# buck_reg_12v_6a.net
KiCad netlist of a schematic drawn in Altium Designer
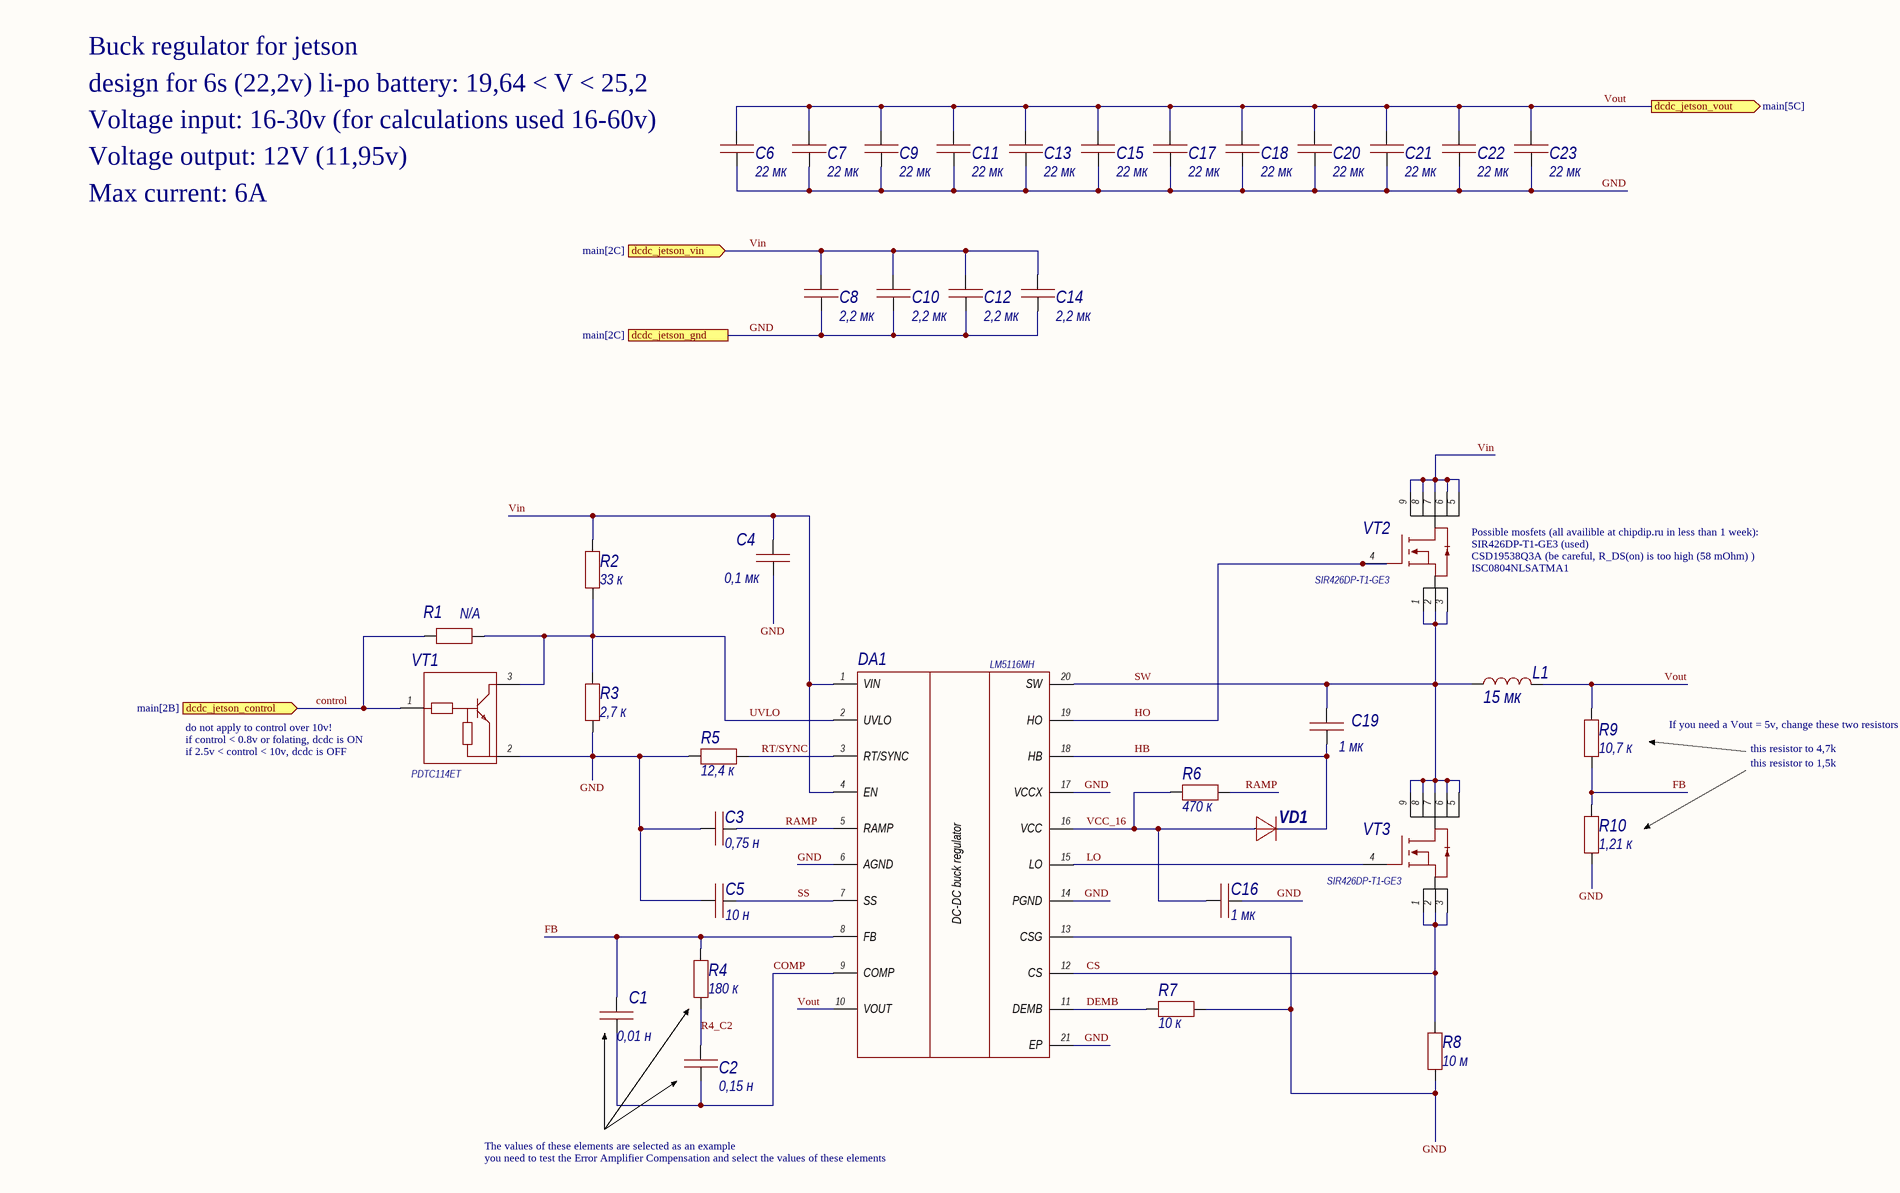
[diagram p0: buck_reg_12v_6a.SchDoc, top left]
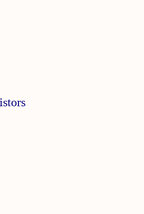
[diagram p1: buck_reg_12v_6a.SchDoc, top right]
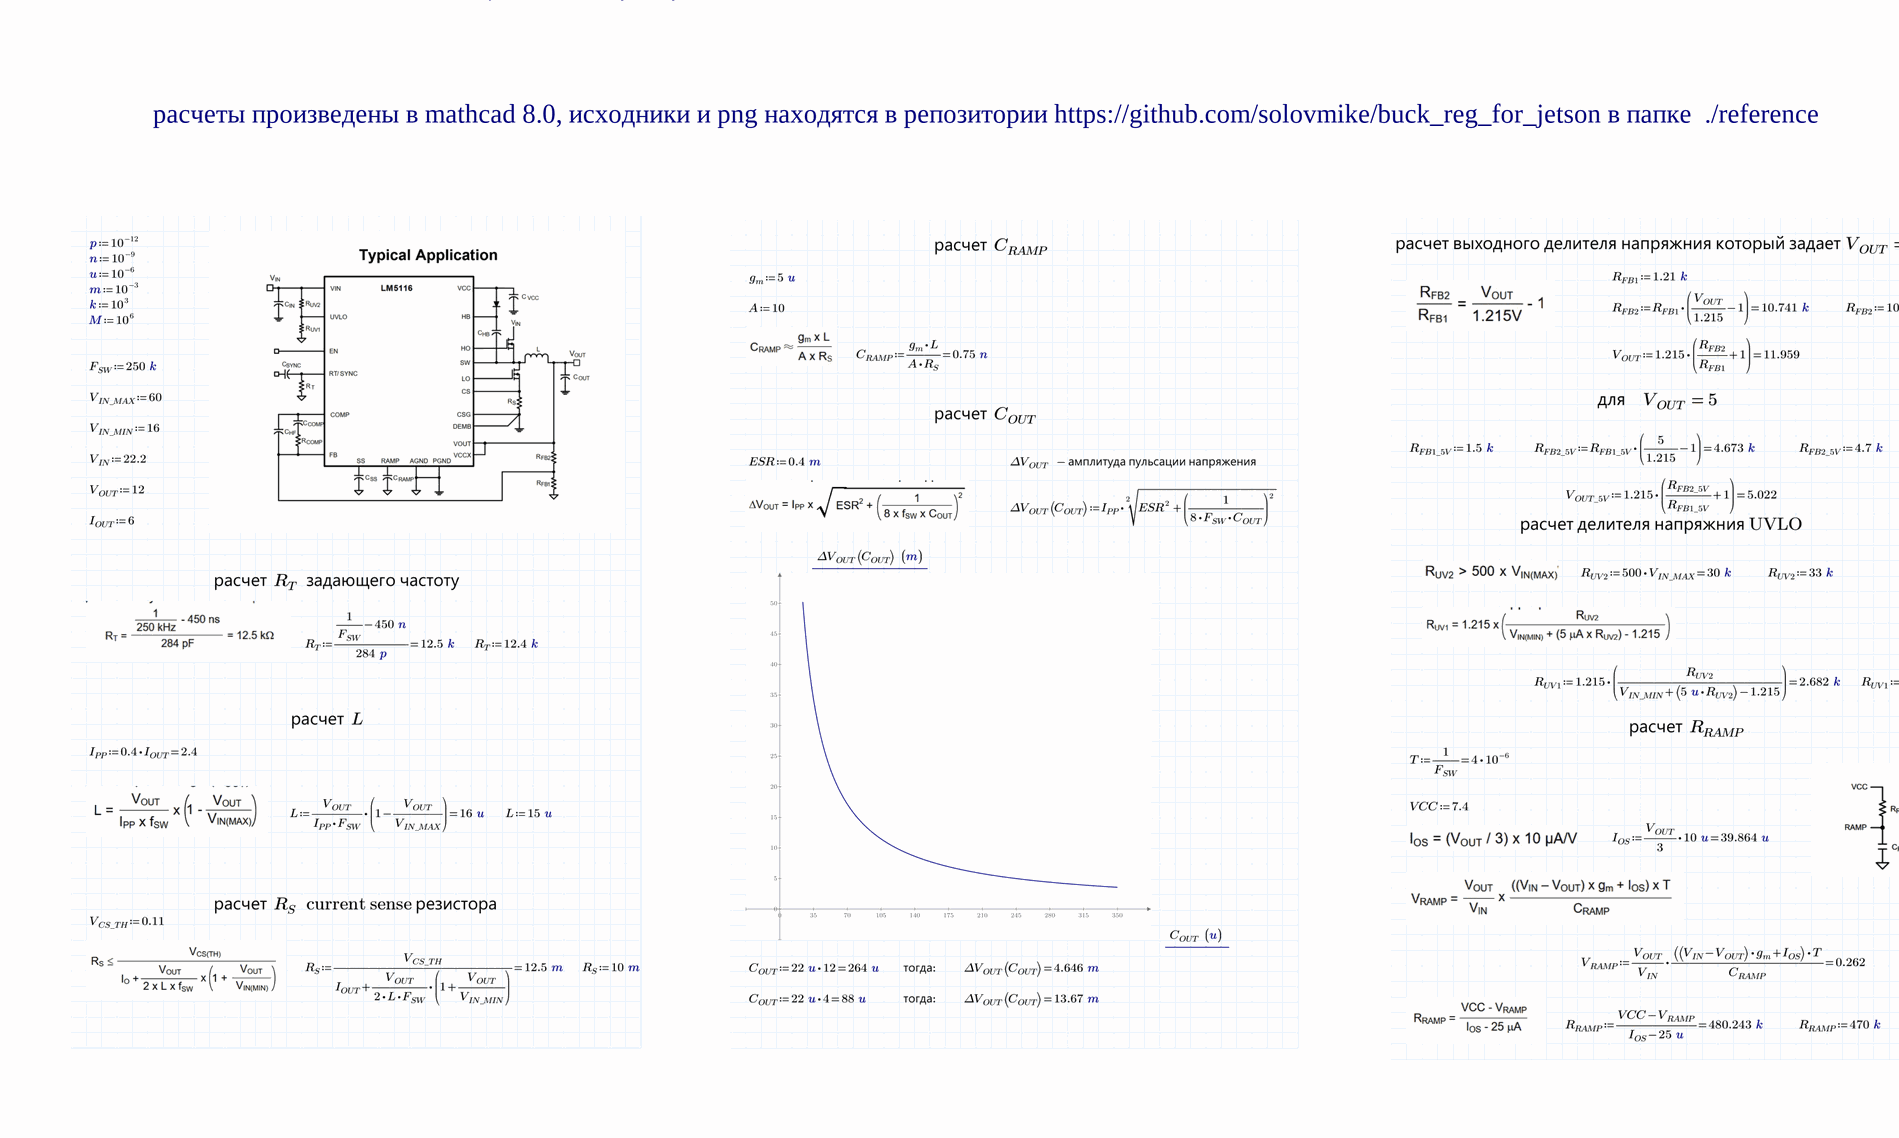
[diagram p2: buck_reg_12v_6a.SchDoc, bottom left]
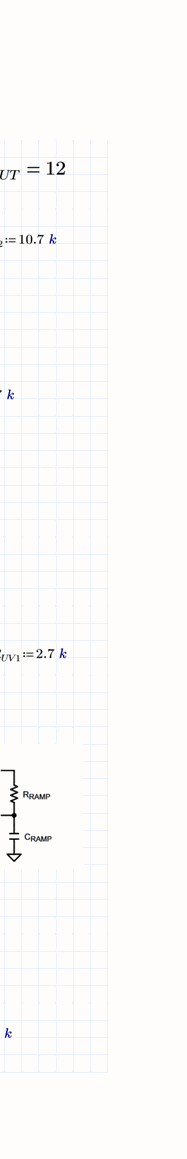
[diagram p3: buck_reg_12v_6a.SchDoc, bottom right]

(export (version "E")
  (design (tool "Eeschema 10.0.6"))
  (components
    (comp (ref "C1")
      (value "0,01 н")
      (footprint "0603C")
      (description "Конденсатор")
      (fields
        (field (name "PART NUMBER") "Capacitor_0,01n_10_50V_X7R_0603C")
        (field (name "TOLERANCE") "0,1")
      )
      (libsource (lib "Hydrolib") (part "Capacitor"))
    )
    (comp (ref "C2")
      (value "0,15 н")
      (footprint "0603C")
      (description "Конденсатор")
      (fields
        (field (name "PART NUMBER") "Capacitor_0,15n_10_50V_X7R_0603C")
        (field (name "TOLERANCE") "0,1")
      )
      (libsource (lib "Hydrolib") (part "Capacitor"))
    )
    (comp (ref "C3")
      (value "0,75 н")
      (footprint "0603C")
      (description "Конденсатор")
      (fields
        (field (name "PART NUMBER") "Capacitor_0,75n_10_50V_X7R_0603C")
        (field (name "TOLERANCE") "0,1")
      )
      (libsource (lib "Hydrolib") (part "Capacitor"))
    )
    (comp (ref "C4")
      (value "0,1 мк")
      (footprint "0603C")
      (description "Конденсатор")
      (fields (field (name "PART NUMBER") "Capacitor_0,1u_10_50V_X7R_0603C") (field (name "TOLERANCE") "0,1"))
      (libsource (lib "Hydrolib") (part "Capacitor"))
    )
    (comp (ref "C5")
      (value "10 н")
      (footprint "0603C")
      (description "Конденсатор")
      (fields (field (name "PART NUMBER") "Capacitor_10n_10_50V_X7R_0603C") (field (name "TOLERANCE") "0,1"))
      (libsource (lib "Hydrolib") (part "Capacitor"))
    )
    (comp (ref "C6")
      (value "22 мк")
      (footprint "1210C")
      (description "Конденсатор")
      (fields (field (name "PART NUMBER") "Capacitor_22u_10_25V_X7R_1210C") (field (name "TOLERANCE") "0,1"))
      (libsource (lib "Hydrolib") (part "Capacitor"))
    )
    (comp (ref "C7")
      (value "22 мк")
      (footprint "1210C")
      (description "Конденсатор")
      (fields (field (name "PART NUMBER") "Capacitor_22u_10_25V_X7R_1210C") (field (name "TOLERANCE") "0,1"))
      (libsource (lib "Hydrolib") (part "Capacitor"))
    )
    (comp (ref "C8")
      (value "2,2 мк")
      (footprint "1206C")
      (description "Конденсатор")
      (fields (field (name "PART NUMBER") "Capacitor_2,2u_10_50V_X7R_1206C") (field (name "TOLERANCE") "0,1"))
      (libsource (lib "Hydrolib") (part "Capacitor"))
    )
    (comp (ref "C9")
      (value "22 мк")
      (footprint "1210C")
      (description "Конденсатор")
      (fields (field (name "PART NUMBER") "Capacitor_22u_10_25V_X7R_1210C") (field (name "TOLERANCE") "0,1"))
      (libsource (lib "Hydrolib") (part "Capacitor"))
    )
    (comp (ref "C10")
      (value "2,2 мк")
      (footprint "1206C")
      (description "Конденсатор")
      (fields (field (name "PART NUMBER") "Capacitor_2,2u_10_50V_X7R_1206C") (field (name "TOLERANCE") "0,1"))
      (libsource (lib "Hydrolib") (part "Capacitor"))
    )
    (comp (ref "C11")
      (value "22 мк")
      (footprint "1210C")
      (description "Конденсатор")
      (fields (field (name "PART NUMBER") "Capacitor_22u_10_25V_X7R_1210C") (field (name "TOLERANCE") "0,1"))
      (libsource (lib "Hydrolib") (part "Capacitor"))
    )
    (comp (ref "C12")
      (value "2,2 мк")
      (footprint "1206C")
      (description "Конденсатор")
      (fields (field (name "PART NUMBER") "Capacitor_2,2u_10_50V_X7R_1206C") (field (name "TOLERANCE") "0,1"))
      (libsource (lib "Hydrolib") (part "Capacitor"))
    )
    (comp (ref "C13")
      (value "22 мк")
      (footprint "1210C")
      (description "Конденсатор")
      (fields (field (name "PART NUMBER") "Capacitor_22u_10_25V_X7R_1210C") (field (name "TOLERANCE") "0,1"))
      (libsource (lib "Hydrolib") (part "Capacitor"))
    )
    (comp (ref "C14")
      (value "2,2 мк")
      (footprint "1206C")
      (description "Конденсатор")
      (fields (field (name "PART NUMBER") "Capacitor_2,2u_10_50V_X7R_1206C") (field (name "TOLERANCE") "0,1"))
      (libsource (lib "Hydrolib") (part "Capacitor"))
    )
    (comp (ref "C15")
      (value "22 мк")
      (footprint "1210C")
      (description "Конденсатор")
      (fields (field (name "PART NUMBER") "Capacitor_22u_10_25V_X7R_1210C") (field (name "TOLERANCE") "0,1"))
      (libsource (lib "Hydrolib") (part "Capacitor"))
    )
    (comp (ref "C16")
      (value "1 мк")
      (footprint "0603C")
      (description "Конденсатор")
      (fields (field (name "PART NUMBER") "Capacitor_1u_10_50V_X7R_0603C") (field (name "TOLERANCE") "0,1"))
      (libsource (lib "Hydrolib") (part "Capacitor"))
    )
    (comp (ref "C17")
      (value "22 мк")
      (footprint "1210C")
      (description "Конденсатор")
      (fields (field (name "PART NUMBER") "Capacitor_22u_10_25V_X7R_1210C") (field (name "TOLERANCE") "0,1"))
      (libsource (lib "Hydrolib") (part "Capacitor"))
    )
    (comp (ref "C18")
      (value "22 мк")
      (footprint "1210C")
      (description "Конденсатор")
      (fields (field (name "PART NUMBER") "Capacitor_22u_10_25V_X7R_1210C") (field (name "TOLERANCE") "0,1"))
      (libsource (lib "Hydrolib") (part "Capacitor"))
    )
    (comp (ref "C19")
      (value "1 мк")
      (footprint "0603C")
      (description "Конденсатор")
      (fields (field (name "PART NUMBER") "Capacitor_1u_10_50V_X7R_0603C") (field (name "TOLERANCE") "0,1"))
      (libsource (lib "Hydrolib") (part "Capacitor"))
    )
    (comp (ref "C20")
      (value "22 мк")
      (footprint "1210C")
      (description "Конденсатор")
      (fields (field (name "PART NUMBER") "Capacitor_22u_10_25V_X7R_1210C") (field (name "TOLERANCE") "0,1"))
      (libsource (lib "Hydrolib") (part "Capacitor"))
    )
    (comp (ref "C21")
      (value "22 мк")
      (footprint "1210C")
      (description "Конденсатор")
      (fields (field (name "PART NUMBER") "Capacitor_22u_10_25V_X7R_1210C") (field (name "TOLERANCE") "0,1"))
      (libsource (lib "Hydrolib") (part "Capacitor"))
    )
    (comp (ref "C22")
      (value "22 мк")
      (footprint "1210C")
      (description "Конденсатор")
      (fields (field (name "PART NUMBER") "Capacitor_22u_10_25V_X7R_1210C") (field (name "TOLERANCE") "0,1"))
      (libsource (lib "Hydrolib") (part "Capacitor"))
    )
    (comp (ref "C23")
      (value "22 мк")
      (footprint "1210C")
      (description "Конденсатор")
      (fields (field (name "PART NUMBER") "Capacitor_22u_10_25V_X7R_1210C") (field (name "TOLERANCE") "0,1"))
      (libsource (lib "Hydrolib") (part "Capacitor"))
    )
    (comp (ref "DA1")
      (value "LM5116MH")
      (footprint "HTSSOP-20")
      (description "dc-dc понижающий adj 6-100v")
      (fields (field (name "MANUFACTURER_PART_NUMBER") "LM5116MH/NOPB"))
      (libsource (lib "Hydrolib") (part "LM5116MH"))
    )
    (comp (ref "L1")
      (value "15 мк")
      (footprint "SPRH127")
      (description "Индуктивность на 15 мкГн, номинальный ток 8,4 А")
      (fields (field (name "PART NUMBER") "CDSPRH127-150M"))
      (libsource (lib "Hydrolib") (part "Inductance"))
    )
    (comp (ref "R1")
      (value "N/A")
      (footprint "0603R")
      (description "посадочное место 0603 под перемычку")
      (fields (field (name "PART NUMBER") "res_0603_N/A") (field (name "TOLERANCE") "1%"))
      (libsource (lib "") (part "Resistor_1"))
    )
    (comp (ref "R2")
      (value "33 к")
      (footprint "0603R")
      (description "Резистор номиналом 33 кОм и точностью 1%")
      (fields (field (name "PART NUMBER") "Resistor_33k_1_0603") (field (name "TOLERANCE") "1%"))
      (libsource (lib "Hydrolib") (part "Resistor"))
    )
    (comp (ref "R3")
      (value "2,7 к")
      (footprint "0603R")
      (description "Резистор номиналом 2,7 кОм и точностью 1%")
      (fields (field (name "PART NUMBER") "Resistor_2.7k_1_0603") (field (name "TOLERANCE") "1%"))
      (libsource (lib "Hydrolib") (part "Resistor"))
    )
    (comp (ref "R4")
      (value "180 к")
      (footprint "0603R")
      (description "Резистор номиналом 180 кОм и точностью 1%")
      (fields (field (name "PART NUMBER") "Resistor_180k_1_0603") (field (name "TOLERANCE") "1%"))
      (libsource (lib "Hydrolib") (part "Resistor"))
    )
    (comp (ref "R5")
      (value "12,4 к")
      (footprint "0603R")
      (description "Резистор номиналом 12,4 кОм и точностью 1%")
      (fields (field (name "PART NUMBER") "Resistor_12.4k_1_0603") (field (name "TOLERANCE") "1%"))
      (libsource (lib "") (part "Resistor_1"))
    )
    (comp (ref "R6")
      (value "470 к")
      (footprint "0603R")
      (description "Резистор номиналом 470 кОм и точностью 1%")
      (fields (field (name "PART NUMBER") "Resistor_470k_1_0603") (field (name "TOLERANCE") "1%"))
      (libsource (lib "") (part "Resistor_1"))
    )
    (comp (ref "R7")
      (value "10 к")
      (footprint "0603R")
      (description "Резистор номиналом 10 кОм и точностью 1%")
      (fields (field (name "PART NUMBER") "Resistor_10k_1_0603") (field (name "TOLERANCE") "1%"))
      (libsource (lib "") (part "Resistor_1"))
    )
    (comp (ref "R8")
      (value "10 м")
      (footprint "1210R")
      (description "Резистор номиналом 10 мОм, точностью 1%, 0.5Вт")
      (fields (field (name "PART NUMBER") "RL1210FR-070R01L") (field (name "TOLERANCE") "1%"))
      (libsource (lib "Hydrolib") (part "Resistor"))
    )
    (comp (ref "R9")
      (value "10,7 к")
      (footprint "0603R")
      (description "Резистор номиналом 10,7 кОм и точностью 1%")
      (fields (field (name "PART NUMBER") "Resistor_10.7k_1_0603") (field (name "TOLERANCE") "1%"))
      (libsource (lib "Hydrolib") (part "Resistor"))
    )
    (comp (ref "R10")
      (value "1,21 к")
      (footprint "0603R")
      (description "Резистор номиналом 1,21 кОм и точностью 1%")
      (fields (field (name "PART NUMBER") "Resistor_1.21k_1_0603") (field (name "TOLERANCE") "1%"))
      (libsource (lib "Hydrolib") (part "Resistor"))
    )
    (comp (ref "VD1")
      (value "ES1D-E3/61T")
      (footprint "SMA")
      (description "Диод 1A 200V")
      (libsource (lib "Hydrolib") (part "Rectifier_diode"))
    )
    (comp (ref "VT1")
      (value "PDTC114ET")
      (footprint "SOT23-3")
      (description "цифровой npn 50в 100мА")
      (libsource (lib "Hydrolib") (part "PDTC114ET"))
    )
    (comp (ref "VT2")
      (value "SIR426DP-T1-GE3")
      (footprint "PowerPAK_SO-8")
      (description "Транзистор полевой MOSFET N-канальный 40В 41.7Вт")
      (libsource (lib "Hydrolib") (part "SIR426DP-T1-GE3"))
    )
    (comp (ref "VT3")
      (value "SIR426DP-T1-GE3")
      (footprint "PowerPAK_SO-8")
      (description "Транзистор полевой MOSFET N-канальный 40В 41.7Вт")
      (libsource (lib "Hydrolib") (part "SIR426DP-T1-GE3"))
    )
  )
  (nets
    (net (code "1") (name "/COMP") (class "Default")
      (node (ref "C1") (pin "1") (pinfunction "1_1") (pintype "passive"))
      (node (ref "C2") (pin "1") (pinfunction "1_1") (pintype "passive"))
      (node (ref "DA1") (pin "9") (pinfunction "COMP_9") (pintype "passive"))
    )
    (net (code "2") (name "/CS") (class "Default")
      (node (ref "DA1") (pin "12") (pinfunction "CS_12") (pintype "passive"))
      (node (ref "R8") (pin "2") (pinfunction "2_2") (pintype "passive"))
      (node (ref "VT3") (pin "1") (pinfunction "1_1") (pintype "passive"))
      (node (ref "VT3") (pin "2") (pinfunction "2_2") (pintype "passive"))
      (node (ref "VT3") (pin "3") (pinfunction "3_3") (pintype "passive"))
    )
    (net (code "3") (name "/DEMB") (class "Default")
      (node (ref "DA1") (pin "11") (pinfunction "DEMB_11") (pintype "passive"))
      (node (ref "R7") (pin "1") (pinfunction "1_1") (pintype "passive"))
    )
    (net (code "4") (name "/FB") (class "Default")
      (node (ref "C1") (pin "2") (pinfunction "2_2") (pintype "passive"))
      (node (ref "DA1") (pin "8") (pinfunction "FB_8") (pintype "passive"))
      (node (ref "R10") (pin "2") (pinfunction "2_2") (pintype "passive"))
      (node (ref "R4") (pin "2") (pinfunction "2_2") (pintype "passive"))
      (node (ref "R9") (pin "1") (pinfunction "1_1") (pintype "passive"))
    )
    (net (code "5") (name "/GND") (class "Default")
      (node (ref "C10") (pin "1") (pinfunction "1_1") (pintype "passive"))
      (node (ref "C11") (pin "1") (pinfunction "1_1") (pintype "passive"))
      (node (ref "C12") (pin "1") (pinfunction "1_1") (pintype "passive"))
      (node (ref "C13") (pin "1") (pinfunction "1_1") (pintype "passive"))
      (node (ref "C14") (pin "1") (pinfunction "1_1") (pintype "passive"))
      (node (ref "C15") (pin "1") (pinfunction "1_1") (pintype "passive"))
      (node (ref "C16") (pin "2") (pinfunction "2_2") (pintype "passive"))
      (node (ref "C17") (pin "1") (pinfunction "1_1") (pintype "passive"))
      (node (ref "C18") (pin "1") (pinfunction "1_1") (pintype "passive"))
      (node (ref "C20") (pin "1") (pinfunction "1_1") (pintype "passive"))
      (node (ref "C21") (pin "1") (pinfunction "1_1") (pintype "passive"))
      (node (ref "C22") (pin "1") (pinfunction "1_1") (pintype "passive"))
      (node (ref "C23") (pin "1") (pinfunction "1_1") (pintype "passive"))
      (node (ref "C3") (pin "1") (pinfunction "1_1") (pintype "passive"))
      (node (ref "C4") (pin "1") (pinfunction "1_1") (pintype "passive"))
      (node (ref "C5") (pin "1") (pinfunction "1_1") (pintype "passive"))
      (node (ref "C6") (pin "1") (pinfunction "1_1") (pintype "passive"))
      (node (ref "C7") (pin "1") (pinfunction "1_1") (pintype "passive"))
      (node (ref "C8") (pin "1") (pinfunction "1_1") (pintype "passive"))
      (node (ref "C9") (pin "1") (pinfunction "1_1") (pintype "passive"))
      (node (ref "DA1") (pin "13") (pinfunction "CSG_13") (pintype "passive"))
      (node (ref "DA1") (pin "14") (pinfunction "PGND_14") (pintype "passive"))
      (node (ref "DA1") (pin "17") (pinfunction "VCCX_17") (pintype "passive"))
      (node (ref "DA1") (pin "21") (pinfunction "EP_21") (pintype "passive"))
      (node (ref "DA1") (pin "6") (pinfunction "AGND_6") (pintype "passive"))
      (node (ref "R10") (pin "1") (pinfunction "1_1") (pintype "passive"))
      (node (ref "R3") (pin "1") (pinfunction "1_1") (pintype "passive"))
      (node (ref "R5") (pin "1") (pinfunction "1_1") (pintype "passive"))
      (node (ref "R7") (pin "2") (pinfunction "2_2") (pintype "passive"))
      (node (ref "R8") (pin "1") (pinfunction "1_1") (pintype "passive"))
      (node (ref "VT1") (pin "2") (pinfunction "E_2") (pintype "passive"))
    )
    (net (code "6") (name "/HB") (class "Default")
      (node (ref "C19") (pin "1") (pinfunction "1_1") (pintype "passive"))
      (node (ref "DA1") (pin "18") (pinfunction "HB_18") (pintype "passive"))
      (node (ref "VD1") (pin "2") (pinfunction "2_2") (pintype "passive"))
    )
    (net (code "7") (name "/HO") (class "Default")
      (node (ref "DA1") (pin "19") (pinfunction "HO_19") (pintype "passive"))
      (node (ref "VT2") (pin "4") (pinfunction "4_4") (pintype "passive"))
    )
    (net (code "8") (name "/LO") (class "Default")
      (node (ref "DA1") (pin "15") (pinfunction "LO_15") (pintype "passive"))
      (node (ref "VT3") (pin "4") (pinfunction "4_4") (pintype "passive"))
    )
    (net (code "9") (name "/R4_C2") (class "Default")
      (node (ref "C2") (pin "2") (pinfunction "2_2") (pintype "passive"))
      (node (ref "R4") (pin "1") (pinfunction "1_1") (pintype "passive"))
    )
    (net (code "10") (name "/RAMP") (class "Default")
      (node (ref "C3") (pin "2") (pinfunction "2_2") (pintype "passive"))
      (node (ref "DA1") (pin "5") (pinfunction "RAMP_5") (pintype "passive"))
      (node (ref "R6") (pin "2") (pinfunction "2_2") (pintype "passive"))
    )
    (net (code "11") (name "/RT{slash}SYNC") (class "Default")
      (node (ref "DA1") (pin "3") (pinfunction "RT/SYNC_3") (pintype "passive"))
      (node (ref "R5") (pin "2") (pinfunction "2_2") (pintype "passive"))
    )
    (net (code "12") (name "/SS") (class "Default")
      (node (ref "C5") (pin "2") (pinfunction "2_2") (pintype "passive"))
      (node (ref "DA1") (pin "7") (pinfunction "SS_7") (pintype "passive"))
    )
    (net (code "13") (name "/SW") (class "Default")
      (node (ref "C19") (pin "2") (pinfunction "2_2") (pintype "passive"))
      (node (ref "DA1") (pin "20") (pinfunction "SW_20") (pintype "passive"))
      (node (ref "L1") (pin "1") (pinfunction "1_1") (pintype "passive"))
      (node (ref "VT2") (pin "1") (pinfunction "1_1") (pintype "passive"))
      (node (ref "VT2") (pin "2") (pinfunction "2_2") (pintype "passive"))
      (node (ref "VT2") (pin "3") (pinfunction "3_3") (pintype "passive"))
      (node (ref "VT3") (pin "5") (pinfunction "5_5") (pintype "passive"))
      (node (ref "VT3") (pin "6") (pinfunction "6_6") (pintype "passive"))
      (node (ref "VT3") (pin "7") (pinfunction "7_7") (pintype "passive"))
      (node (ref "VT3") (pin "8") (pinfunction "8_8") (pintype "passive"))
      (node (ref "VT3") (pin "9") (pinfunction "9_9") (pintype "passive"))
    )
    (net (code "14") (name "/UVLO") (class "Default")
      (node (ref "DA1") (pin "2") (pinfunction "UVLO_2") (pintype "passive"))
      (node (ref "R1") (pin "2") (pinfunction "2_2") (pintype "passive"))
      (node (ref "R2") (pin "1") (pinfunction "1_1") (pintype "passive"))
      (node (ref "R3") (pin "2") (pinfunction "2_2") (pintype "passive"))
      (node (ref "VT1") (pin "3") (pinfunction "C_3") (pintype "passive"))
    )
    (net (code "15") (name "/VCC_16") (class "Default")
      (node (ref "C16") (pin "1") (pinfunction "1_1") (pintype "passive"))
      (node (ref "DA1") (pin "16") (pinfunction "VCC_16") (pintype "passive"))
      (node (ref "R6") (pin "1") (pinfunction "1_1") (pintype "passive"))
      (node (ref "VD1") (pin "1") (pinfunction "1_1") (pintype "passive"))
    )
    (net (code "16") (name "/Vin") (class "Default")
      (node (ref "C10") (pin "2") (pinfunction "2_2") (pintype "passive"))
      (node (ref "C12") (pin "2") (pinfunction "2_2") (pintype "passive"))
      (node (ref "C14") (pin "2") (pinfunction "2_2") (pintype "passive"))
      (node (ref "C4") (pin "2") (pinfunction "2_2") (pintype "passive"))
      (node (ref "C8") (pin "2") (pinfunction "2_2") (pintype "passive"))
      (node (ref "DA1") (pin "1") (pinfunction "VIN_1") (pintype "passive"))
      (node (ref "DA1") (pin "4") (pinfunction "EN_4") (pintype "passive"))
      (node (ref "R2") (pin "2") (pinfunction "2_2") (pintype "passive"))
      (node (ref "VT2") (pin "5") (pinfunction "5_5") (pintype "passive"))
      (node (ref "VT2") (pin "6") (pinfunction "6_6") (pintype "passive"))
      (node (ref "VT2") (pin "7") (pinfunction "7_7") (pintype "passive"))
      (node (ref "VT2") (pin "8") (pinfunction "8_8") (pintype "passive"))
      (node (ref "VT2") (pin "9") (pinfunction "9_9") (pintype "passive"))
    )
    (net (code "17") (name "/Vout") (class "Default")
      (node (ref "C11") (pin "2") (pinfunction "2_2") (pintype "passive"))
      (node (ref "C13") (pin "2") (pinfunction "2_2") (pintype "passive"))
      (node (ref "C15") (pin "2") (pinfunction "2_2") (pintype "passive"))
      (node (ref "C17") (pin "2") (pinfunction "2_2") (pintype "passive"))
      (node (ref "C18") (pin "2") (pinfunction "2_2") (pintype "passive"))
      (node (ref "C20") (pin "2") (pinfunction "2_2") (pintype "passive"))
      (node (ref "C21") (pin "2") (pinfunction "2_2") (pintype "passive"))
      (node (ref "C22") (pin "2") (pinfunction "2_2") (pintype "passive"))
      (node (ref "C23") (pin "2") (pinfunction "2_2") (pintype "passive"))
      (node (ref "C6") (pin "2") (pinfunction "2_2") (pintype "passive"))
      (node (ref "C7") (pin "2") (pinfunction "2_2") (pintype "passive"))
      (node (ref "C9") (pin "2") (pinfunction "2_2") (pintype "passive"))
      (node (ref "DA1") (pin "10") (pinfunction "VOUT_10") (pintype "passive"))
      (node (ref "L1") (pin "2") (pinfunction "2_2") (pintype "passive"))
      (node (ref "R9") (pin "2") (pinfunction "2_2") (pintype "passive"))
    )
    (net (code "18") (name "/control") (class "Default")
      (node (ref "R1") (pin "1") (pinfunction "1_1") (pintype "passive"))
      (node (ref "VT1") (pin "1") (pinfunction "B_1") (pintype "passive"))
    )
  )
)
